# EMG_Sensors_Control.net
KiCad netlist of a schematic drawn in Altium Designer
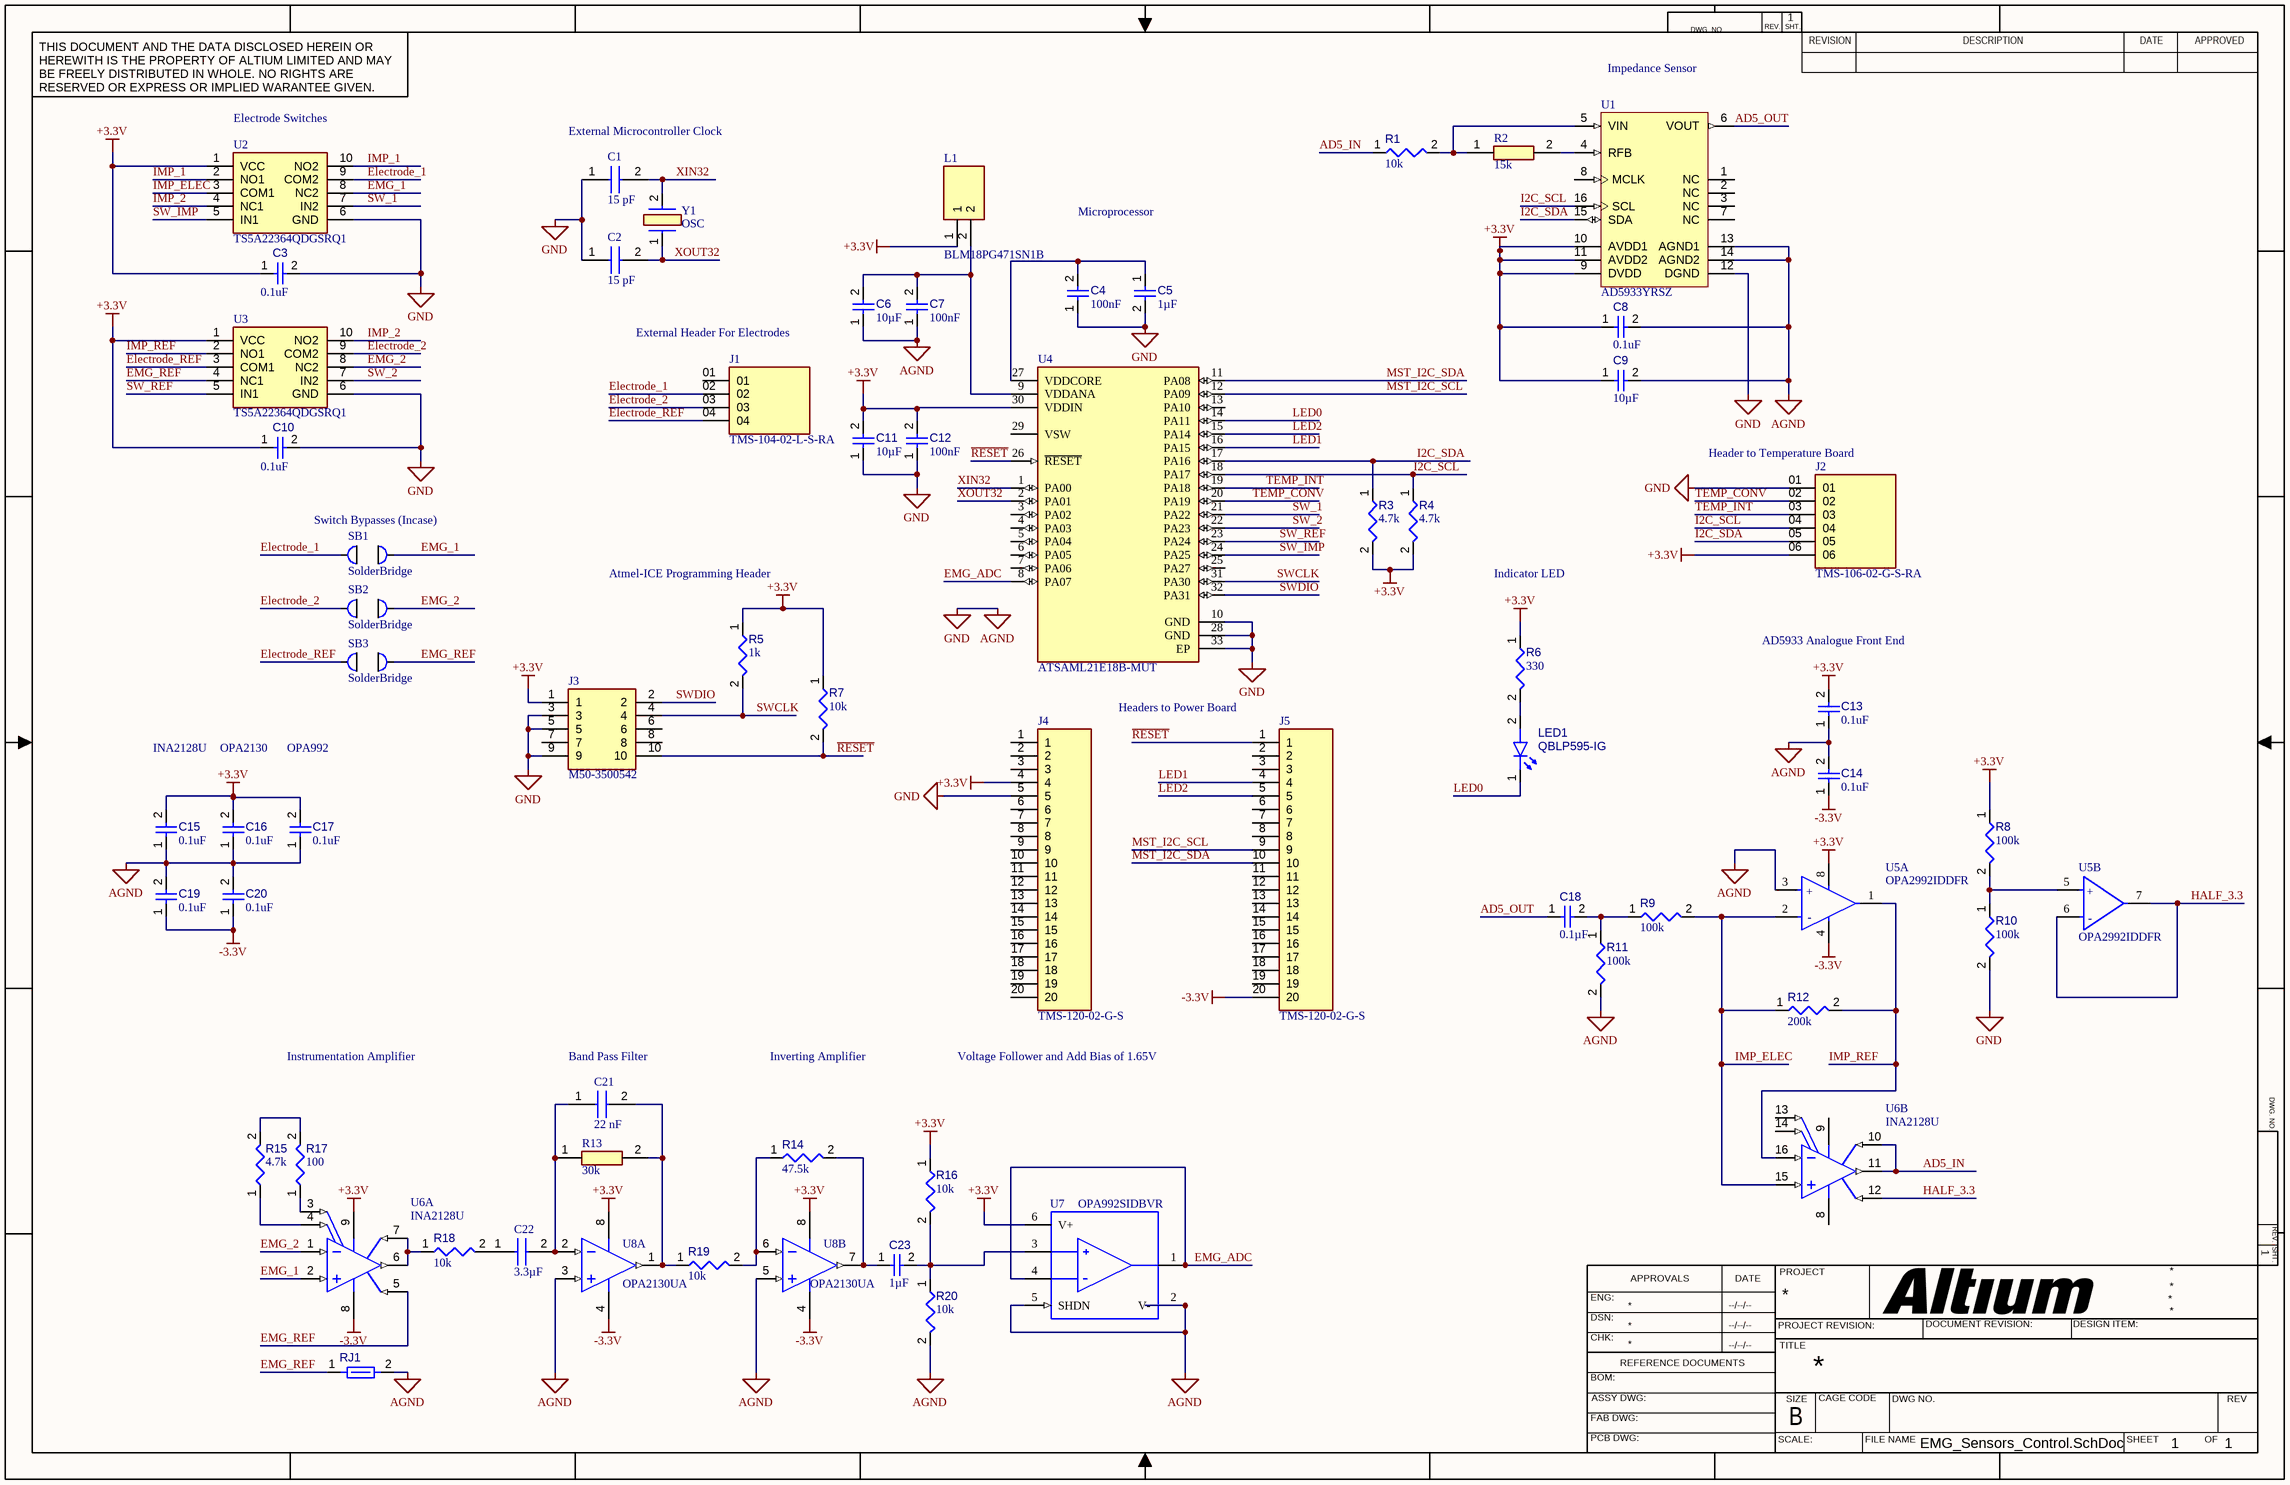
[diagram p0: EMG_Sensors_Control.SchDoc]

(export (version "E")
  (design (tool "Eeschema 10.0.6"))
  (components
    (comp (ref "C1")
      (value "15 pF")
      (footprint "SamacSys:CAPC1005X55N")
      (description "Capacitor 15PF 50V 5% 0402GCM1555C1H150JA16D")
      (fields
        (field (name "MANUFACTURER_PART_NUMBER") "GCM1555C1H150JA16D")
        (field (name "MOUSER PART NUMBER") "81-GCM1555C1H150JA6D")
      )
      (libsource (lib "*") (part "GCM1555C1H150JA16D"))
    )
    (comp (ref "C2")
      (value "15 pF")
      (footprint "SamacSys:CAPC1005X55N")
      (description "Capacitor 15PF 50V 5% 0402GCM1555C1H150JA16D")
      (fields
        (field (name "MANUFACTURER_PART_NUMBER") "GCM1555C1H150JA16D")
        (field (name "MOUSER PART NUMBER") "81-GCM1555C1H150JA6D")
      )
      (libsource (lib "*") (part "GCM1555C1H150JA16D"))
    )
    (comp (ref "C3")
      (value "0.1uF")
      (footprint "CAPC1005X56X25LL10T15")
      (description "Chip Capacitor, 0.1 uF, +/- 5%, 16 V, 0402 (1005 Metric)")
      (fields (field (name "TOLERANCE") "5%") (field (name "Comment") "Capacitor 0.1 uF +/- 5% 16 V 0402"))
      (libsource (lib "Education") (part "CAP-NP-2"))
    )
    (comp (ref "C4")
      (value "100nF")
      (footprint "CAPC1005X56X25LL10T15")
      (description "Chip Capacitor, 0.1 uF, +/- 5%, 16 V, 0402 (1005 Metric)")
      (fields (field (name "TOLERANCE") "5%") (field (name "Comment") "Capacitor 0.1 uF +/- 5% 16 V 0402"))
      (libsource (lib "Education") (part "CAP-NP-2"))
    )
    (comp (ref "C5")
      (value "1µF")
      (footprint "CAPC1608X90X35ML15T15")
      (description "Chip Capacitor, 1 uF, +/- 10%, 16 V, 0603 (1608 Metric)")
      (fields (field (name "TOLERANCE") "10%") (field (name "Comment") "Capacitor 1uF +/- 10% 16V 0603"))
      (libsource (lib "Education") (part "CAP-NP-2"))
    )
    (comp (ref "C6")
      (value "10µF")
      (footprint "CAPC2013X135X45NL10T25")
      (description "Chip Capacitor, 10 uF, +/- 10%, 16 V, 0805 (2012 Metric)")
      (fields (field (name "TOLERANCE") "10%") (field (name "Comment") "Capacitor 10 uF +/- 10% 16 V 0805"))
      (libsource (lib "Education") (part "CAP-NP-2"))
    )
    (comp (ref "C7")
      (value "100nF")
      (footprint "CAPC1005X56X25LL10T15")
      (description "Chip Capacitor, 0.1 uF, +/- 5%, 16 V, 0402 (1005 Metric)")
      (fields (field (name "TOLERANCE") "5%") (field (name "Comment") "Capacitor 0.1 uF +/- 5% 16 V 0402"))
      (libsource (lib "Education") (part "CAP-NP-2"))
    )
    (comp (ref "C8")
      (value "0.1uF")
      (footprint "CAPC1005X56X25LL10T15")
      (description "Chip Capacitor, 0.1 uF, +/- 5%, 16 V, 0402 (1005 Metric)")
      (fields (field (name "TOLERANCE") "5%") (field (name "Comment") "Capacitor 0.1 uF +/- 5% 16 V 0402"))
      (libsource (lib "Education") (part "CAP-NP-2"))
    )
    (comp (ref "C9")
      (value "10µF")
      (footprint "CAPC0603(1608)100_L")
      (description "Chip Capacitor, 10µF +/-20%, 10V, 0603, Thickness 1 mm")
      (fields (field (name "TOLERANCE") "10%") (field (name "Comment") "Capacitor 10µF +/-20% 10V 0603"))
      (libsource (lib "Education") (part "CAP-NP-2"))
    )
    (comp (ref "C10")
      (value "0.1uF")
      (footprint "CAPC1005X56X25LL10T15")
      (description "Chip Capacitor, 0.1 uF, +/- 5%, 16 V, 0402 (1005 Metric)")
      (fields (field (name "TOLERANCE") "5%") (field (name "Comment") "Capacitor 0.1 uF +/- 5% 16 V 0402"))
      (libsource (lib "Education") (part "CAP-NP-2"))
    )
    (comp (ref "C11")
      (value "10µF")
      (footprint "CAPC2013X135X45NL10T25")
      (description "Chip Capacitor, 10 uF, +/- 10%, 16 V, 0805 (2012 Metric)")
      (fields (field (name "TOLERANCE") "10%") (field (name "Comment") "Capacitor 10 uF +/- 10% 16 V 0805"))
      (libsource (lib "Education") (part "CAP-NP-2"))
    )
    (comp (ref "C12")
      (value "100nF")
      (footprint "CAPC1005X56X25LL10T15")
      (description "Chip Capacitor, 0.1 uF, +/- 5%, 16 V, 0402 (1005 Metric)")
      (fields (field (name "TOLERANCE") "5%") (field (name "Comment") "Capacitor 0.1 uF +/- 5% 16 V 0402"))
      (libsource (lib "Education") (part "CAP-NP-2"))
    )
    (comp (ref "C13")
      (value "0.1uF")
      (footprint "CAPC1005X56X25LL10T15")
      (description "Chip Capacitor, 0.1 uF, +/- 5%, 16 V, 0402 (1005 Metric)")
      (fields (field (name "TOLERANCE") "5%") (field (name "Comment") "Capacitor 0.1 uF +/- 5% 16 V 0402"))
      (libsource (lib "Education") (part "CAP-NP-2"))
    )
    (comp (ref "C14")
      (value "0.1uF")
      (footprint "CAPC1005X56X25LL10T15")
      (description "Chip Capacitor, 0.1 uF, +/- 5%, 16 V, 0402 (1005 Metric)")
      (fields (field (name "TOLERANCE") "5%") (field (name "Comment") "Capacitor 0.1 uF +/- 5% 16 V 0402"))
      (libsource (lib "Education") (part "CAP-NP-2"))
    )
    (comp (ref "C15")
      (value "0.1uF")
      (footprint "CAPC1005X56X25LL10T15")
      (description "Chip Capacitor, 0.1 uF, +/- 5%, 16 V, 0402 (1005 Metric)")
      (fields (field (name "TOLERANCE") "5%") (field (name "Comment") "Capacitor 0.1 uF +/- 5% 16 V 0402"))
      (libsource (lib "Education") (part "CAP-NP-2"))
    )
    (comp (ref "C16")
      (value "0.1uF")
      (footprint "CAPC1005X56X25LL10T15")
      (description "Chip Capacitor, 0.1 uF, +/- 5%, 16 V, 0402 (1005 Metric)")
      (fields (field (name "TOLERANCE") "5%") (field (name "Comment") "Capacitor 0.1 uF +/- 5% 16 V 0402"))
      (libsource (lib "Education") (part "CAP-NP-2"))
    )
    (comp (ref "C17")
      (value "0.1uF")
      (footprint "CAPC1005X56X25LL10T15")
      (description "Chip Capacitor, 0.1 uF, +/- 5%, 16 V, 0402 (1005 Metric)")
      (fields (field (name "TOLERANCE") "5%") (field (name "Comment") "Capacitor 0.1 uF +/- 5% 16 V 0402"))
      (libsource (lib "Education") (part "CAP-NP-2"))
    )
    (comp (ref "C18")
      (value "0.1µF")
      (footprint "CAPC1005X55X25LL05T10")
      (description "Chip Capacitor, 1 uF, +/- 10%, 6.3 V, 0402 (1005 Metric)")
      (fields (field (name "TOLERANCE") "10%") (field (name "Comment") "Capacitor 1 uF +/- 10% 6.3 V 0402"))
      (libsource (lib "Education") (part "CAP-NP-2"))
    )
    (comp (ref "C19")
      (value "0.1uF")
      (footprint "CAPC1005X56X25LL10T15")
      (description "Chip Capacitor, 0.1 uF, +/- 5%, 16 V, 0402 (1005 Metric)")
      (fields (field (name "TOLERANCE") "5%") (field (name "Comment") "Capacitor 0.1 uF +/- 5% 16 V 0402"))
      (libsource (lib "Education") (part "CAP-NP-2"))
    )
    (comp (ref "C20")
      (value "0.1uF")
      (footprint "CAPC1005X56X25LL10T15")
      (description "Chip Capacitor, 0.1 uF, +/- 5%, 16 V, 0402 (1005 Metric)")
      (fields (field (name "TOLERANCE") "5%") (field (name "Comment") "Capacitor 0.1 uF +/- 5% 16 V 0402"))
      (libsource (lib "Education") (part "CAP-NP-2"))
    )
    (comp (ref "C21")
      (value "22 nF")
      (footprint "SamacSys:CAPC1005X55N")
      (description "Capacitor 22nF")
      (fields
        (field (name "MANUFACTURER_PART_NUMBER") "GRM155R70J222KA01D")
        (field (name "MOUSER PART NUMBER") "81-GRM155R70J222KA1D")
      )
      (libsource (lib "*") (part "GRM155R70J222KA01D"))
    )
    (comp (ref "C22")
      (value "3.3µF")
      (footprint "SamacSys:C1005_Commercial")
      (description "Capacitor 3.3uF C1005X5R0J335K050BC")
      (fields
        (field (name "MANUFACTURER_PART_NUMBER") "C1005X5R0J335K050BC")
        (field (name "MOUSER PART NUMBER") "810-C1005X5R0J335K")
      )
      (libsource (lib "*") (part "C1005X5R0J335K050BC"))
    )
    (comp (ref "C23")
      (value "1µF")
      (footprint "CAPC1005X55X25LL05T10")
      (description "Chip Capacitor, 1 uF, +/- 10%, 6.3 V, 0402 (1005 Metric)")
      (fields (field (name "TOLERANCE") "10%") (field (name "Comment") "Capacitor 1 uF +/- 10% 6.3 V 0402"))
      (libsource (lib "Education") (part "CAP-NP-2"))
    )
    (comp (ref "J1")
      (value "TMS-104-02-L-S-RA")
      (footprint "SAMTEC_TMS-104-02-L-S-RA")
      (libsource (lib "TMS-104-02-L-S-RA") (part "TMS-104-02-L-S-RA"))
    )
    (comp (ref "J2")
      (value "TMS-106-02-G-S-RA")
      (footprint "SAMTEC_TMS-106-02-G-S-RA")
      (libsource (lib "TMS-106-02-G-S-RA") (part "TMS-106-02-G-S-RA"))
    )
    (comp (ref "J3")
      (value "M50-3500542")
      (footprint "SamacSys:M503500542")
      (description "Connector M50-3500542")
      (fields (field (name "MOUSER PART NUMBER") "855-M50-3500542"))
      (libsource (lib "*") (part "M50-3500542"))
    )
    (comp (ref "J4")
      (value "TMS-120-02-G-S")
      (footprint "SamacSys:TMS-120-YY-XX-S")
      (description "Connector - male needed, place on top board TMS-120-02-G-S")
      (fields (field (name "MOUSER PART NUMBER") "200-TMS12002GS"))
      (libsource (lib "SamacSys") (part "TMS-120-02-G-S"))
    )
    (comp (ref "J5")
      (value "TMS-120-02-G-S")
      (footprint "SamacSys:TMS-120-YY-XX-S")
      (description "Connector - male needed, place on top board TMS-120-02-G-S")
      (fields (field (name "MOUSER PART NUMBER") "200-TMS12002GS"))
      (libsource (lib "SamacSys") (part "TMS-120-02-G-S"))
    )
    (comp (ref "L1")
      (value "BLM18PG471SN1B")
      (footprint "SamacSys:BLM18AG102BH1D")
      (description "Filter BLM18PG471SN1B")
      (fields (field (name "MOUSER PART NUMBER") "81-BLM18PG471SN1B"))
      (libsource (lib "*") (part "BLM18PG471SN1B"))
    )
    (comp (ref "LED1")
      (value "QBLP595-IG")
      (footprint "QTB-QBLP595_V")
      (libsource (lib "Education") (part "LED-KA-2"))
    )
    (comp (ref "R1")
      (value "10k")
      (footprint "RESC1005X40X25ML05T05")
      (description "Chip Resistor, 10 KOhm, +/- 1%, 63 mW, -55 to 155 degC, 0402 (1005 Metric)")
      (fields (field (name "POWER") "63mW") (field (name "TOLERANCE") "1%"))
      (libsource (lib "Education") (part "RES-2"))
    )
    (comp (ref "R2")
      (value "15k")
      (footprint "SamacSys:H2C/H2R")
      (description "Resistor  ERJ-H2RD1502X")
      (fields (field (name "MANUFACTURER_PART_NUMBER") "ERJ-H2RD1502X"))
      (libsource (lib "*") (part "ERJ-H2RD1502X"))
    )
    (comp (ref "R3")
      (value "4.7k")
      (footprint "RESC1005X40X25ML05T05")
      (description "Chip Resistor, 4.7 KOhm, +/- 1%, 0.1 W, -55 to 155 degC, 0402 (1005 Metric)")
      (fields (field (name "POWER") "100mW") (field (name "TOLERANCE") "1%"))
      (libsource (lib "Education") (part "RES-2"))
    )
    (comp (ref "R4")
      (value "4.7k")
      (footprint "RESC1005X40X25ML05T05")
      (description "Chip Resistor, 4.7 KOhm, +/- 1%, 0.1 W, -55 to 155 degC, 0402 (1005 Metric)")
      (fields (field (name "POWER") "100mW") (field (name "TOLERANCE") "1%"))
      (libsource (lib "Education") (part "RES-2"))
    )
    (comp (ref "R5")
      (value "1k")
      (footprint "RESC1005X40X25ML05T05")
      (description "Chip Resistor, 1 KOhm, +/- 1%, 63 mW, -55 to 155 degC, 0402 (1005 Metric)")
      (fields (field (name "POWER") "63mW") (field (name "TOLERANCE") "1%"))
      (libsource (lib "Education") (part "RES-2"))
    )
    (comp (ref "R6")
      (value "330")
      (footprint "RESC0402(1005)_L")
      (description "Chip Resistor, 330 Ohms, +/-5 %, 63 mW, -55 to 155 degC, 0402")
      (fields (field (name "POWER") "63mW") (field (name "TOLERANCE") "5%"))
      (libsource (lib "Education") (part "RES-2"))
    )
    (comp (ref "R7")
      (value "10k")
      (footprint "RESC1005X40X25ML05T05")
      (description "Chip Resistor, 10 KOhm, +/- 1%, 63 mW, -55 to 155 degC, 0402 (1005 Metric)")
      (fields (field (name "POWER") "63mW") (field (name "TOLERANCE") "1%"))
      (libsource (lib "Education") (part "RES-2"))
    )
    (comp (ref "R8")
      (value "100k")
      (footprint "RESC1005X40X25ML05T05")
      (description "Chip Resistor, 100 KOhm, +/- 1%, 0.063 W, -55 to 155 degC, 0402 (1005 Metric)")
      (fields (field (name "TOLERANCE") "1%") (field (name "POWER") "63mW"))
      (libsource (lib "Education") (part "RES-2"))
    )
    (comp (ref "R9")
      (value "100k")
      (footprint "RESC1005X40X25ML05T05")
      (description "Chip Resistor, 100 KOhm, +/- 1%, 0.063 W, -55 to 155 degC, 0402 (1005 Metric)")
      (fields (field (name "TOLERANCE") "1%") (field (name "POWER") "63mW"))
      (libsource (lib "Education") (part "RES-2"))
    )
    (comp (ref "R10")
      (value "100k")
      (footprint "RESC1005X40X25ML05T05")
      (description "Chip Resistor, 100 KOhm, +/- 1%, 0.063 W, -55 to 155 degC, 0402 (1005 Metric)")
      (fields (field (name "TOLERANCE") "1%") (field (name "POWER") "63mW"))
      (libsource (lib "Education") (part "RES-2"))
    )
    (comp (ref "R11")
      (value "100k")
      (footprint "RESC1005X40X25ML05T05")
      (description "Chip Resistor, 1 KOhm, +/- 1%, 63 mW, -55 to 155 degC, 0402 (1005 Metric)")
      (fields (field (name "POWER") "63mW") (field (name "TOLERANCE") "1%"))
      (libsource (lib "Education") (part "RES-2"))
    )
    (comp (ref "R12")
      (value "200k")
      (footprint "RESC0402(1005)_L")
      (description "Chip Resistor, 1 MOhms, +/-1 %, 63 mW, -55 to 155 degC, 0402")
      (fields (field (name "TOLERANCE") "1%") (field (name "POWER") "63mW"))
      (libsource (lib "Education") (part "RES-2"))
    )
    (comp (ref "R13")
      (value "30k")
      (footprint "SamacSys:RESC1005X40N")
      (description "Resistor 30k 0402 SFR01MZPJ303")
      (fields (field (name "MANUFACTURER_PART_NUMBER") "SFR01MZPJ303"))
      (libsource (lib "*") (part "SFR01MZPJ303"))
    )
    (comp (ref "R14")
      (value "47.5k")
      (footprint "RESC0402(1005)_L")
      (description "Chip Resistor, 47,5 kOhms, +/-1 %, 63 mW, -55 to 155 degC, 0402")
      (fields (field (name "POWER") "63mW") (field (name "TOLERANCE") "1%"))
      (libsource (lib "Education") (part "RES-2"))
    )
    (comp (ref "R15")
      (value "4.7k")
      (footprint "RESC1005X40X25ML05T05")
      (description "Chip Resistor, 4.7 KOhm, +/- 1%, 0.1 W, -55 to 155 degC, 0402 (1005 Metric)")
      (fields (field (name "POWER") "100mW") (field (name "TOLERANCE") "1%"))
      (libsource (lib "Education") (part "RES-2"))
    )
    (comp (ref "R16")
      (value "10k")
      (footprint "RESC1005X40X25ML05T05")
      (description "Chip Resistor, 10 KOhm, +/- 1%, 63 mW, -55 to 155 degC, 0402 (1005 Metric)")
      (fields (field (name "POWER") "63mW") (field (name "TOLERANCE") "1%"))
      (libsource (lib "Education") (part "RES-2"))
    )
    (comp (ref "R17")
      (value "100")
      (footprint "RESC0402(1005)_L")
      (description "100R 0.063W 1% 0402 (1005 Metric)  SMD")
      (fields (field (name "TOLERANCE") "1%") (field (name "POWER") "63mW"))
      (libsource (lib "Education") (part "100R2F"))
    )
    (comp (ref "R18")
      (value "10k")
      (footprint "RESC1005X40X25ML05T05")
      (description "Chip Resistor, 10 KOhm, +/- 1%, 63 mW, -55 to 155 degC, 0402 (1005 Metric)")
      (fields (field (name "POWER") "63mW") (field (name "TOLERANCE") "1%"))
      (libsource (lib "Education") (part "RES-2"))
    )
    (comp (ref "R19")
      (value "10k")
      (footprint "RESC1005X40X25ML05T05")
      (description "Chip Resistor, 10 KOhm, +/- 1%, 63 mW, -55 to 155 degC, 0402 (1005 Metric)")
      (fields (field (name "POWER") "63mW") (field (name "TOLERANCE") "1%"))
      (libsource (lib "Education") (part "RES-2"))
    )
    (comp (ref "R20")
      (value "10k")
      (footprint "RESC1005X40X25ML05T05")
      (description "Chip Resistor, 10 KOhm, +/- 1%, 63 mW, -55 to 155 degC, 0402 (1005 Metric)")
      (fields (field (name "POWER") "63mW") (field (name "TOLERANCE") "1%"))
      (libsource (lib "Education") (part "RES-2"))
    )
    (comp (ref "RJ1")
      (value "Net Tie 10x8mil")
      (footprint "New footprint 1")
      (libsource (lib "Education") (part "CMP-00022-00002-2"))
    )
    (comp (ref "SB1")
      (value "SolderBridge")
      (footprint "SolderBridge-Footprint-1")
      (description "Simple open solder bridge")
      (libsource (lib "Education") (part "SolderBridge"))
    )
    (comp (ref "SB2")
      (value "SolderBridge")
      (footprint "SolderBridge-Footprint-1")
      (description "Simple open solder bridge")
      (libsource (lib "Education") (part "SolderBridge"))
    )
    (comp (ref "SB3")
      (value "SolderBridge")
      (footprint "SolderBridge-Footprint-1")
      (description "Simple open solder bridge")
      (libsource (lib "Education") (part "SolderBridge"))
    )
    (comp (ref "U1")
      (value "AD5933YRSZ")
      (footprint "ADI-RS-16_L")
      (description "1 MSPS, 12-Bit Impedance Converter, Network Analyzer, Serial, RS-16, 77 Tube, Pb-Free")
      (libsource (lib "Altium Content Vault") (part "ADI-AD5933-RS-16"))
    )
    (comp (ref "U2")
      (value "TS5A22364QDGSRQ1")
      (footprint "SamacSys:SOP50P490X110-10N")
      (description "Integrated Circuit")
      (fields (field (name "MOUSER PART NUMBER") "595-TS5A22364QDGSRQ1"))
      (libsource (lib "*") (part "TS5A22364QDGSRQ1"))
    )
    (comp (ref "U3")
      (value "TS5A22364QDGSRQ1")
      (footprint "SamacSys:SOP50P490X110-10N")
      (description "Integrated Circuit")
      (fields (field (name "MOUSER PART NUMBER") "595-TS5A22364QDGSRQ1"))
      (libsource (lib "*") (part "TS5A22364QDGSRQ1"))
    )
    (comp (ref "U4")
      (value "ATSAML21E18B-MUT")
      (footprint "FP-PG-IPC_B")
      (description "IC MCU 32BIT 256KB FLASH 32QFN")
      (libsource (lib "Altium Content Vault") (part "b79c866f022c195cb18a64dbd2a129a"))
    )
    (comp (ref "U5")
      (value "OPA2992IDDFR")
      (footprint "FP-DDF0008A-MFG")
      (description "IC OPAMP GP 2 CIRCUIT TSOT23-8")
      (libsource (lib "Altium Content Vault") (part "d5b36c1049528187b1d2197d5d58d7e"))
    )
    (comp (ref "U6")
      (value "INA2128U")
      (footprint "DW0016A_N")
      (fields (field (name "MANUFACTURER") "Texas Instruments"))
      (libsource (lib "Altium Content Vault") (part "TI-INA212XXXX16"))
    )
    (comp (ref "U7")
      (value "OPA992SIDBVR")
      (footprint "FP-DBV0006A-MFG")
      (description "IC OPAMP")
      (libsource (lib "Altium Content Vault") (part "a02ce2c64a2dc138dd09b28dc7c79e9"))
    )
    (comp (ref "U8")
      (value "OPA2130UA")
      (footprint "D0008A_N")
      (fields (field (name "MANUFACTURER") "Texas Instruments"))
      (libsource (lib "Altium Content Vault") (part "TI-OPA-8_2"))
    )
    (comp (ref "Y1")
      (value "OSC")
      (footprint "SamacSys:ABS0716632768KHZT")
      (description "Crystal or Oscillator ABS07-32.768KHZ-T 12.5pF")
      (fields
        (field (name "MANUFACTURER_PART_NUMBER") "ABS07-32.768KHZ-T")
        (field (name "MOUSER PART NUMBER") "815-ABS07-32.768KHZT")
      )
      (libsource (lib "*") (part "ABS07-32.768KHZ-T"))
    )
  )
  (nets
    (net (code "1") (name "+3.3V") (class "Default")
      (node (ref "C10") (pin "1") (pinfunction "1_1") (pintype "passive"))
      (node (ref "C11") (pin "2") (pinfunction "2_2") (pintype "passive"))
      (node (ref "C12") (pin "2") (pinfunction "2_2") (pintype "passive"))
      (node (ref "C13") (pin "2") (pinfunction "2_2") (pintype "passive"))
      (node (ref "C15") (pin "2") (pinfunction "2_2") (pintype "passive"))
      (node (ref "C16") (pin "2") (pinfunction "2_2") (pintype "passive"))
      (node (ref "C17") (pin "2") (pinfunction "2_2") (pintype "passive"))
      (node (ref "C3") (pin "1") (pinfunction "1_1") (pintype "passive"))
      (node (ref "C8") (pin "1") (pinfunction "1_1") (pintype "passive"))
      (node (ref "C9") (pin "1") (pinfunction "1_1") (pintype "passive"))
      (node (ref "J2") (pin "06") (pinfunction "06_06") (pintype "passive"))
      (node (ref "J3") (pin "1") (pinfunction "1_1") (pintype "passive"))
      (node (ref "J4") (pin "4") (pinfunction "4_4") (pintype "passive"))
      (node (ref "L1") (pin "1") (pinfunction "1_1") (pintype "passive"))
      (node (ref "R16") (pin "1") (pinfunction "1_1") (pintype "passive"))
      (node (ref "R3") (pin "2") (pinfunction "2_2") (pintype "passive"))
      (node (ref "R4") (pin "2") (pinfunction "2_2") (pintype "passive"))
      (node (ref "R5") (pin "1") (pinfunction "1_1") (pintype "passive"))
      (node (ref "R6") (pin "1") (pinfunction "1_1") (pintype "passive"))
      (node (ref "R7") (pin "1") (pinfunction "1_1") (pintype "passive"))
      (node (ref "R8") (pin "1") (pinfunction "1_1") (pintype "passive"))
      (node (ref "U1") (pin "10") (pinfunction "AVDD1_10") (pintype "power_in"))
      (node (ref "U1") (pin "11") (pinfunction "AVDD2_11") (pintype "power_in"))
      (node (ref "U1") (pin "9") (pinfunction "DVDD_9") (pintype "power_in"))
      (node (ref "U2") (pin "1") (pinfunction "VCC_1") (pintype "passive"))
      (node (ref "U3") (pin "1") (pinfunction "VCC_1") (pintype "passive"))
      (node (ref "U4") (pin "30") (pinfunction "VDDIN_30") (pintype "power_in"))
      (node (ref "U5") (pin "8") (pinfunction "V+_8") (pintype "power_in"))
      (node (ref "U6") (pin "9") (pinfunction "V+_9") (pintype "power_in"))
      (node (ref "U7") (pin "6") (pinfunction "V+_6") (pintype "power_in"))
      (node (ref "U8") (pin "8") (pinfunction "V+_8") (pintype "power_in"))
    )
    (net (code "2") (name "-3.3V") (class "Default")
      (node (ref "C14") (pin "1") (pinfunction "1_1") (pintype "passive"))
      (node (ref "C19") (pin "1") (pinfunction "1_1") (pintype "passive"))
      (node (ref "C20") (pin "1") (pinfunction "1_1") (pintype "passive"))
      (node (ref "J5") (pin "20") (pinfunction "20_20") (pintype "passive"))
      (node (ref "U5") (pin "4") (pinfunction "V-_4") (pintype "power_in"))
      (node (ref "U6") (pin "8") (pinfunction "V-_8") (pintype "power_in"))
      (node (ref "U8") (pin "4") (pinfunction "V-_4") (pintype "power_in"))
    )
    (net (code "3") (name "/AD5_IN") (class "Default")
      (node (ref "R1") (pin "1") (pinfunction "1_1") (pintype "passive"))
      (node (ref "U6") (pin "10") (pinfunction "SENSEB_10") (pintype "input"))
      (node (ref "U6") (pin "11") (pinfunction "VOB_11") (pintype "output"))
    )
    (net (code "4") (name "/AD5_OUT") (class "Default")
      (node (ref "C18") (pin "1") (pinfunction "1_1") (pintype "passive"))
      (node (ref "U1") (pin "6") (pinfunction "VOUT_6") (pintype "output"))
    )
    (net (code "5") (name "/EMG_1") (class "Default")
      (node (ref "SB1") (pin "1") (pinfunction "1_1") (pintype "passive"))
      (node (ref "U2") (pin "8") (pinfunction "NC2_8") (pintype "passive"))
      (node (ref "U6") (pin "2") (pinfunction "VINA+_2") (pintype "input"))
    )
    (net (code "6") (name "/EMG_2") (class "Default")
      (node (ref "SB2") (pin "1") (pinfunction "1_1") (pintype "passive"))
      (node (ref "U3") (pin "8") (pinfunction "NC2_8") (pintype "passive"))
      (node (ref "U6") (pin "1") (pinfunction "VINA-_1") (pintype "input"))
    )
    (net (code "7") (name "/EMG_ADC") (class "Default")
      (node (ref "U4") (pin "8") (pinfunction "PA07_8") (pintype "bidirectional"))
      (node (ref "U7") (pin "1") (pinfunction "OUT_1") (pintype "passive"))
      (node (ref "U7") (pin "4") (pinfunction "-IN_4") (pintype "tri_state"))
    )
    (net (code "8") (name "/EMG_REF") (class "Default")
      (node (ref "RJ1") (pin "1") (pinfunction "1_1") (pintype "passive"))
      (node (ref "SB3") (pin "1") (pinfunction "1_1") (pintype "passive"))
      (node (ref "U3") (pin "4") (pinfunction "NC1_4") (pintype "passive"))
      (node (ref "U6") (pin "5") (pinfunction "REFA_5") (pintype "input"))
    )
    (net (code "9") (name "/Electrode_1") (class "Default")
      (node (ref "J1") (pin "02") (pinfunction "02_02") (pintype "passive"))
      (node (ref "SB1") (pin "2") (pinfunction "2_2") (pintype "passive"))
      (node (ref "U2") (pin "9") (pinfunction "COM2_9") (pintype "passive"))
    )
    (net (code "10") (name "/Electrode_2") (class "Default")
      (node (ref "J1") (pin "03") (pinfunction "03_03") (pintype "passive"))
      (node (ref "SB2") (pin "2") (pinfunction "2_2") (pintype "passive"))
      (node (ref "U3") (pin "9") (pinfunction "COM2_9") (pintype "passive"))
    )
    (net (code "11") (name "/Electrode_REF") (class "Default")
      (node (ref "J1") (pin "04") (pinfunction "04_04") (pintype "passive"))
      (node (ref "SB3") (pin "2") (pinfunction "2_2") (pintype "passive"))
      (node (ref "U3") (pin "3") (pinfunction "COM1_3") (pintype "passive"))
    )
    (net (code "12") (name "/HALF_3.3") (class "Default")
      (node (ref "U5") (pin "6") (pinfunction "IN2-_6") (pintype "tri_state"))
      (node (ref "U5") (pin "7") (pinfunction "OUT2_7") (pintype "passive"))
      (node (ref "U6") (pin "12") (pinfunction "REFB_12") (pintype "input"))
    )
    (net (code "13") (name "/I2C_SCL") (class "Default")
      (node (ref "J2") (pin "04") (pinfunction "04_04") (pintype "passive"))
      (node (ref "R4") (pin "1") (pinfunction "1_1") (pintype "passive"))
      (node (ref "U1") (pin "16") (pinfunction "SCL_16") (pintype "input"))
      (node (ref "U4") (pin "18") (pinfunction "PA17_18") (pintype "bidirectional"))
    )
    (net (code "14") (name "/I2C_SDA") (class "Default")
      (node (ref "J2") (pin "05") (pinfunction "05_05") (pintype "passive"))
      (node (ref "R3") (pin "1") (pinfunction "1_1") (pintype "passive"))
      (node (ref "U1") (pin "15") (pinfunction "SDA_15") (pintype "bidirectional"))
      (node (ref "U4") (pin "17") (pinfunction "PA16_17") (pintype "bidirectional"))
    )
    (net (code "15") (name "/IMP_1") (class "Default")
      (node (ref "U2") (pin "10") (pinfunction "NO2_10") (pintype "passive"))
      (node (ref "U2") (pin "2") (pinfunction "NO1_2") (pintype "passive"))
    )
    (net (code "16") (name "/IMP_2") (class "Default")
      (node (ref "U2") (pin "4") (pinfunction "NC1_4") (pintype "passive"))
      (node (ref "U3") (pin "10") (pinfunction "NO2_10") (pintype "passive"))
    )
    (net (code "17") (name "/IMP_ELEC") (class "Default")
      (node (ref "R12") (pin "1") (pinfunction "1_1") (pintype "passive"))
      (node (ref "R9") (pin "2") (pinfunction "2_2") (pintype "passive"))
      (node (ref "U2") (pin "3") (pinfunction "COM1_3") (pintype "passive"))
      (node (ref "U5") (pin "2") (pinfunction "IN1-_2") (pintype "tri_state"))
      (node (ref "U6") (pin "15") (pinfunction "VINB+_15") (pintype "input"))
    )
    (net (code "18") (name "/IMP_REF") (class "Default")
      (node (ref "R12") (pin "2") (pinfunction "2_2") (pintype "passive"))
      (node (ref "U3") (pin "2") (pinfunction "NO1_2") (pintype "passive"))
      (node (ref "U5") (pin "1") (pinfunction "OUT1_1") (pintype "passive"))
      (node (ref "U6") (pin "16") (pinfunction "VINB-_16") (pintype "input"))
    )
    (net (code "19") (name "/LED0") (class "Default")
      (node (ref "LED1") (pin "1") (pinfunction "K_1") (pintype "passive"))
      (node (ref "U4") (pin "14") (pinfunction "PA11_14") (pintype "bidirectional"))
    )
    (net (code "20") (name "/LED1") (class "Default")
      (node (ref "J5") (pin "4") (pinfunction "4_4") (pintype "passive"))
      (node (ref "U4") (pin "16") (pinfunction "PA15_16") (pintype "bidirectional"))
    )
    (net (code "21") (name "/LED2") (class "Default")
      (node (ref "J5") (pin "5") (pinfunction "5_5") (pintype "passive"))
      (node (ref "U4") (pin "15") (pinfunction "PA14_15") (pintype "bidirectional"))
    )
    (net (code "22") (name "/MST_I2C_SCL") (class "Default")
      (node (ref "J5") (pin "9") (pinfunction "9_9") (pintype "passive"))
      (node (ref "U4") (pin "12") (pinfunction "PA09_12") (pintype "bidirectional"))
    )
    (net (code "23") (name "/MST_I2C_SDA") (class "Default")
      (node (ref "J5") (pin "10") (pinfunction "10_10") (pintype "passive"))
      (node (ref "U4") (pin "11") (pinfunction "PA08_11") (pintype "bidirectional"))
    )
    (net (code "24") (name "/SWCLK") (class "Default")
      (node (ref "J3") (pin "4") (pinfunction "4_4") (pintype "passive"))
      (node (ref "R5") (pin "2") (pinfunction "2_2") (pintype "passive"))
      (node (ref "U4") (pin "31") (pinfunction "PA30_31") (pintype "bidirectional"))
    )
    (net (code "25") (name "/SWDIO") (class "Default")
      (node (ref "J3") (pin "2") (pinfunction "2_2") (pintype "passive"))
      (node (ref "U4") (pin "32") (pinfunction "PA31_32") (pintype "bidirectional"))
    )
    (net (code "26") (name "/SW_1") (class "Default")
      (node (ref "U2") (pin "7") (pinfunction "IN2_7") (pintype "passive"))
      (node (ref "U4") (pin "21") (pinfunction "PA22_21") (pintype "bidirectional"))
    )
    (net (code "27") (name "/SW_2") (class "Default")
      (node (ref "U3") (pin "7") (pinfunction "IN2_7") (pintype "passive"))
      (node (ref "U4") (pin "22") (pinfunction "PA23_22") (pintype "bidirectional"))
    )
    (net (code "28") (name "/SW_IMP") (class "Default")
      (node (ref "U2") (pin "5") (pinfunction "IN1_5") (pintype "passive"))
      (node (ref "U4") (pin "24") (pinfunction "PA25_24") (pintype "bidirectional"))
    )
    (net (code "29") (name "/SW_REF") (class "Default")
      (node (ref "U3") (pin "5") (pinfunction "IN1_5") (pintype "passive"))
      (node (ref "U4") (pin "23") (pinfunction "PA24_23") (pintype "bidirectional"))
    )
    (net (code "30") (name "/TEMP_CONV") (class "Default")
      (node (ref "J2") (pin "02") (pinfunction "02_02") (pintype "passive"))
      (node (ref "U4") (pin "20") (pinfunction "PA19_20") (pintype "bidirectional"))
    )
    (net (code "31") (name "/TEMP_INT") (class "Default")
      (node (ref "J2") (pin "03") (pinfunction "03_03") (pintype "passive"))
      (node (ref "U4") (pin "19") (pinfunction "PA18_19") (pintype "bidirectional"))
    )
    (net (code "32") (name "/XIN32") (class "Default")
      (node (ref "C1") (pin "2") (pinfunction "2_2") (pintype "passive"))
      (node (ref "U4") (pin "1") (pinfunction "PA00_1") (pintype "bidirectional"))
      (node (ref "Y1") (pin "2") (pinfunction "2_2") (pintype "passive"))
    )
    (net (code "33") (name "/XOUT32") (class "Default")
      (node (ref "C2") (pin "2") (pinfunction "2_2") (pintype "passive"))
      (node (ref "U4") (pin "2") (pinfunction "PA01_2") (pintype "bidirectional"))
      (node (ref "Y1") (pin "1") (pinfunction "1_1") (pintype "passive"))
    )
    (net (code "34") (name "/~{RESET}") (class "Default")
      (node (ref "J3") (pin "10") (pinfunction "10_10") (pintype "passive"))
      (node (ref "J5") (pin "1") (pinfunction "1_1") (pintype "passive"))
      (node (ref "R7") (pin "2") (pinfunction "2_2") (pintype "passive"))
      (node (ref "U4") (pin "26") (pinfunction "~{RESET}_26") (pintype "input"))
    )
    (net (code "35") (name "AGND") (class "Default")
      (node (ref "C1") (pin "1") (pinfunction "1_1") (pintype "passive"))
      (node (ref "C10") (pin "2") (pinfunction "2_2") (pintype "passive"))
      (node (ref "C11") (pin "1") (pinfunction "1_1") (pintype "passive"))
      (node (ref "C12") (pin "1") (pinfunction "1_1") (pintype "passive"))
      (node (ref "C13") (pin "1") (pinfunction "1_1") (pintype "passive"))
      (node (ref "C14") (pin "2") (pinfunction "2_2") (pintype "passive"))
      (node (ref "C15") (pin "1") (pinfunction "1_1") (pintype "passive"))
      (node (ref "C16") (pin "1") (pinfunction "1_1") (pintype "passive"))
      (node (ref "C17") (pin "1") (pinfunction "1_1") (pintype "passive"))
      (node (ref "C19") (pin "2") (pinfunction "2_2") (pintype "passive"))
      (node (ref "C2") (pin "1") (pinfunction "1_1") (pintype "passive"))
      (node (ref "C20") (pin "2") (pinfunction "2_2") (pintype "passive"))
      (node (ref "C3") (pin "2") (pinfunction "2_2") (pintype "passive"))
      (node (ref "C4") (pin "1") (pinfunction "1_1") (pintype "passive"))
      (node (ref "C5") (pin "2") (pinfunction "2_2") (pintype "passive"))
      (node (ref "C6") (pin "1") (pinfunction "1_1") (pintype "passive"))
      (node (ref "C7") (pin "1") (pinfunction "1_1") (pintype "passive"))
      (node (ref "C8") (pin "2") (pinfunction "2_2") (pintype "passive"))
      (node (ref "C9") (pin "2") (pinfunction "2_2") (pintype "passive"))
      (node (ref "J2") (pin "01") (pinfunction "01_01") (pintype "passive"))
      (node (ref "J3") (pin "3") (pinfunction "3_3") (pintype "passive"))
      (node (ref "J3") (pin "5") (pinfunction "5_5") (pintype "passive"))
      (node (ref "J3") (pin "9") (pinfunction "9_9") (pintype "passive"))
      (node (ref "J4") (pin "5") (pinfunction "5_5") (pintype "passive"))
      (node (ref "R10") (pin "2") (pinfunction "2_2") (pintype "passive"))
      (node (ref "R11") (pin "2") (pinfunction "2_2") (pintype "passive"))
      (node (ref "R20") (pin "2") (pinfunction "2_2") (pintype "passive"))
      (node (ref "RJ1") (pin "2") (pinfunction "2_2") (pintype "passive"))
      (node (ref "U1") (pin "12") (pinfunction "DGND_12") (pintype "power_in"))
      (node (ref "U1") (pin "13") (pinfunction "AGND1_13") (pintype "power_in"))
      (node (ref "U1") (pin "14") (pinfunction "AGND2_14") (pintype "power_in"))
      (node (ref "U2") (pin "6") (pinfunction "GND_6") (pintype "passive"))
      (node (ref "U3") (pin "6") (pinfunction "GND_6") (pintype "passive"))
      (node (ref "U4") (pin "10") (pinfunction "GND_10") (pintype "power_in"))
      (node (ref "U4") (pin "28") (pinfunction "GND_28") (pintype "power_in"))
      (node (ref "U4") (pin "33") (pinfunction "EP_33") (pintype "passive"))
      (node (ref "U5") (pin "3") (pinfunction "IN1+_3") (pintype "tri_state"))
      (node (ref "U7") (pin "2") (pinfunction "V-_2") (pintype "power_in"))
      (node (ref "U7") (pin "5") (pinfunction "SHDN_5") (pintype "input"))
      (node (ref "U8") (pin "3") (pinfunction "IN_A+_3") (pintype "input"))
      (node (ref "U8") (pin "5") (pinfunction "IN_B+_5") (pintype "input"))
    )
    (net (code "36") (name "Net-(C18-Pad2)") (class "Default")
      (node (ref "C18") (pin "2") (pinfunction "2_2") (pintype "passive"))
      (node (ref "R11") (pin "1") (pinfunction "1_1") (pintype "passive"))
      (node (ref "R9") (pin "1") (pinfunction "1_1") (pintype "passive"))
    )
    (net (code "37") (name "Net-(C22-Pad1)") (class "Default")
      (node (ref "C22") (pin "1") (pinfunction "1_1") (pintype "passive"))
      (node (ref "R18") (pin "2") (pinfunction "2_2") (pintype "passive"))
    )
    (net (code "38") (name "Net-(LED1-A)") (class "Default")
      (node (ref "LED1") (pin "2") (pinfunction "A_2") (pintype "passive"))
      (node (ref "R6") (pin "2") (pinfunction "2_2") (pintype "passive"))
    )
    (net (code "39") (name "Net-(R15-Pad1)") (class "Default")
      (node (ref "R15") (pin "1") (pinfunction "1_1") (pintype "passive"))
      (node (ref "U6") (pin "4") (pinfunction "RGA_4") (pintype "input"))
    )
    (net (code "40") (name "Net-(R15-Pad2)") (class "Default")
      (node (ref "R15") (pin "2") (pinfunction "2_2") (pintype "passive"))
      (node (ref "R17") (pin "2") (pinfunction "2_2") (pintype "passive"))
    )
    (net (code "41") (name "Net-(R17-Pad1)") (class "Default")
      (node (ref "R17") (pin "1") (pinfunction "1_1") (pintype "passive"))
      (node (ref "U6") (pin "3") (pinfunction "RGA_3") (pintype "input"))
    )
    (net (code "42") (name "Net-(U1-RFB)") (class "Default")
      (node (ref "R2") (pin "2") (pinfunction "2_2") (pintype "passive"))
      (node (ref "U1") (pin "4") (pinfunction "RFB_4") (pintype "input"))
    )
    (net (code "43") (name "Net-(U1-VIN)") (class "Default")
      (node (ref "R1") (pin "2") (pinfunction "2_2") (pintype "passive"))
      (node (ref "R2") (pin "1") (pinfunction "1_1") (pintype "passive"))
      (node (ref "U1") (pin "5") (pinfunction "VIN_5") (pintype "input"))
    )
    (net (code "44") (name "Net-(U4-VDDANA)") (class "Default")
      (node (ref "C6") (pin "2") (pinfunction "2_2") (pintype "passive"))
      (node (ref "C7") (pin "2") (pinfunction "2_2") (pintype "passive"))
      (node (ref "L1") (pin "2") (pinfunction "2_2") (pintype "passive"))
      (node (ref "U4") (pin "9") (pinfunction "VDDANA_9") (pintype "power_in"))
    )
    (net (code "45") (name "Net-(U4-VDDCORE)") (class "Default")
      (node (ref "C4") (pin "2") (pinfunction "2_2") (pintype "passive"))
      (node (ref "C5") (pin "1") (pinfunction "1_1") (pintype "passive"))
      (node (ref "U4") (pin "27") (pinfunction "VDDCORE_27") (pintype "power_in"))
    )
    (net (code "46") (name "Net-(U5B-IN2+)") (class "Default")
      (node (ref "R10") (pin "1") (pinfunction "1_1") (pintype "passive"))
      (node (ref "R8") (pin "2") (pinfunction "2_2") (pintype "passive"))
      (node (ref "U5") (pin "5") (pinfunction "IN2+_5") (pintype "tri_state"))
    )
    (net (code "47") (name "Net-(U6A-SENSEA)") (class "Default")
      (node (ref "R18") (pin "1") (pinfunction "1_1") (pintype "passive"))
      (node (ref "U6") (pin "6") (pinfunction "VOA_6") (pintype "output"))
      (node (ref "U6") (pin "7") (pinfunction "SENSEA_7") (pintype "input"))
    )
    (net (code "48") (name "Net-(U7-+IN)") (class "Default")
      (node (ref "C23") (pin "2") (pinfunction "2_2") (pintype "passive"))
      (node (ref "R16") (pin "2") (pinfunction "2_2") (pintype "passive"))
      (node (ref "R20") (pin "1") (pinfunction "1_1") (pintype "passive"))
      (node (ref "U7") (pin "3") (pinfunction "+IN_3") (pintype "tri_state"))
    )
    (net (code "49") (name "Net-(U8A-IN_A-)") (class "Default")
      (node (ref "C21") (pin "1") (pinfunction "1_1") (pintype "passive"))
      (node (ref "C22") (pin "2") (pinfunction "2_2") (pintype "passive"))
      (node (ref "R13") (pin "1") (pinfunction "1_1") (pintype "passive"))
      (node (ref "U8") (pin "2") (pinfunction "IN_A-_2") (pintype "input"))
    )
    (net (code "50") (name "Net-(U8A-OUT_A)") (class "Default")
      (node (ref "C21") (pin "2") (pinfunction "2_2") (pintype "passive"))
      (node (ref "R13") (pin "2") (pinfunction "2_2") (pintype "passive"))
      (node (ref "R19") (pin "1") (pinfunction "1_1") (pintype "passive"))
      (node (ref "U8") (pin "1") (pinfunction "OUT_A_1") (pintype "output"))
    )
    (net (code "51") (name "Net-(U8B-IN_B-)") (class "Default")
      (node (ref "R14") (pin "1") (pinfunction "1_1") (pintype "passive"))
      (node (ref "R19") (pin "2") (pinfunction "2_2") (pintype "passive"))
      (node (ref "U8") (pin "6") (pinfunction "IN_B-_6") (pintype "input"))
    )
    (net (code "52") (name "Net-(U8B-OUT_B)") (class "Default")
      (node (ref "C23") (pin "1") (pinfunction "1_1") (pintype "passive"))
      (node (ref "R14") (pin "2") (pinfunction "2_2") (pintype "passive"))
      (node (ref "U8") (pin "7") (pinfunction "OUT_B_7") (pintype "output"))
    )
    (net (code "53") (name "unconnected-(J1-Pad01)") (class "Default")
      (node (ref "J1") (pin "01") (pinfunction "01_01") (pintype "passive"))
    )
    (net (code "54") (name "unconnected-(J3-Pad6)") (class "Default")
      (node (ref "J3") (pin "6") (pinfunction "6_6") (pintype "passive"))
    )
    (net (code "55") (name "unconnected-(J3-Pad7)") (class "Default")
      (node (ref "J3") (pin "7") (pinfunction "7_7") (pintype "passive"))
    )
    (net (code "56") (name "unconnected-(J3-Pad8)") (class "Default")
      (node (ref "J3") (pin "8") (pinfunction "8_8") (pintype "passive"))
    )
    (net (code "57") (name "unconnected-(J4-Pad1)") (class "Default")
      (node (ref "J4") (pin "1") (pinfunction "1_1") (pintype "passive"))
    )
    (net (code "58") (name "unconnected-(J4-Pad2)") (class "Default")
      (node (ref "J4") (pin "2") (pinfunction "2_2") (pintype "passive"))
    )
    (net (code "59") (name "unconnected-(J4-Pad3)") (class "Default")
      (node (ref "J4") (pin "3") (pinfunction "3_3") (pintype "passive"))
    )
    (net (code "60") (name "unconnected-(J4-Pad6)") (class "Default")
      (node (ref "J4") (pin "6") (pinfunction "6_6") (pintype "passive"))
    )
    (net (code "61") (name "unconnected-(J4-Pad7)") (class "Default")
      (node (ref "J4") (pin "7") (pinfunction "7_7") (pintype "passive"))
    )
    (net (code "62") (name "unconnected-(J4-Pad8)") (class "Default")
      (node (ref "J4") (pin "8") (pinfunction "8_8") (pintype "passive"))
    )
    (net (code "63") (name "unconnected-(J4-Pad9)") (class "Default")
      (node (ref "J4") (pin "9") (pinfunction "9_9") (pintype "passive"))
    )
    (net (code "64") (name "unconnected-(J4-Pad10)") (class "Default")
      (node (ref "J4") (pin "10") (pinfunction "10_10") (pintype "passive"))
    )
    (net (code "65") (name "unconnected-(J4-Pad11)") (class "Default")
      (node (ref "J4") (pin "11") (pinfunction "11_11") (pintype "passive"))
    )
    (net (code "66") (name "unconnected-(J4-Pad12)") (class "Default")
      (node (ref "J4") (pin "12") (pinfunction "12_12") (pintype "passive"))
    )
    (net (code "67") (name "unconnected-(J4-Pad13)") (class "Default")
      (node (ref "J4") (pin "13") (pinfunction "13_13") (pintype "passive"))
    )
    (net (code "68") (name "unconnected-(J4-Pad14)") (class "Default")
      (node (ref "J4") (pin "14") (pinfunction "14_14") (pintype "passive"))
    )
    (net (code "69") (name "unconnected-(J4-Pad15)") (class "Default")
      (node (ref "J4") (pin "15") (pinfunction "15_15") (pintype "passive"))
    )
    (net (code "70") (name "unconnected-(J4-Pad16)") (class "Default")
      (node (ref "J4") (pin "16") (pinfunction "16_16") (pintype "passive"))
    )
    (net (code "71") (name "unconnected-(J4-Pad17)") (class "Default")
      (node (ref "J4") (pin "17") (pinfunction "17_17") (pintype "passive"))
    )
    (net (code "72") (name "unconnected-(J4-Pad18)") (class "Default")
      (node (ref "J4") (pin "18") (pinfunction "18_18") (pintype "passive"))
    )
    (net (code "73") (name "unconnected-(J4-Pad19)") (class "Default")
      (node (ref "J4") (pin "19") (pinfunction "19_19") (pintype "passive"))
    )
    (net (code "74") (name "unconnected-(J4-Pad20)") (class "Default")
      (node (ref "J4") (pin "20") (pinfunction "20_20") (pintype "passive"))
    )
    (net (code "75") (name "unconnected-(J5-Pad2)") (class "Default")
      (node (ref "J5") (pin "2") (pinfunction "2_2") (pintype "passive"))
    )
    (net (code "76") (name "unconnected-(J5-Pad3)") (class "Default")
      (node (ref "J5") (pin "3") (pinfunction "3_3") (pintype "passive"))
    )
    (net (code "77") (name "unconnected-(J5-Pad6)") (class "Default")
      (node (ref "J5") (pin "6") (pinfunction "6_6") (pintype "passive"))
    )
    (net (code "78") (name "unconnected-(J5-Pad7)") (class "Default")
      (node (ref "J5") (pin "7") (pinfunction "7_7") (pintype "passive"))
    )
    (net (code "79") (name "unconnected-(J5-Pad8)") (class "Default")
      (node (ref "J5") (pin "8") (pinfunction "8_8") (pintype "passive"))
    )
    (net (code "80") (name "unconnected-(J5-Pad11)") (class "Default")
      (node (ref "J5") (pin "11") (pinfunction "11_11") (pintype "passive"))
    )
    (net (code "81") (name "unconnected-(J5-Pad12)") (class "Default")
      (node (ref "J5") (pin "12") (pinfunction "12_12") (pintype "passive"))
    )
    (net (code "82") (name "unconnected-(J5-Pad13)") (class "Default")
      (node (ref "J5") (pin "13") (pinfunction "13_13") (pintype "passive"))
    )
    (net (code "83") (name "unconnected-(J5-Pad14)") (class "Default")
      (node (ref "J5") (pin "14") (pinfunction "14_14") (pintype "passive"))
    )
    (net (code "84") (name "unconnected-(J5-Pad15)") (class "Default")
      (node (ref "J5") (pin "15") (pinfunction "15_15") (pintype "passive"))
    )
    (net (code "85") (name "unconnected-(J5-Pad16)") (class "Default")
      (node (ref "J5") (pin "16") (pinfunction "16_16") (pintype "passive"))
    )
    (net (code "86") (name "unconnected-(J5-Pad17)") (class "Default")
      (node (ref "J5") (pin "17") (pinfunction "17_17") (pintype "passive"))
    )
    (net (code "87") (name "unconnected-(J5-Pad18)") (class "Default")
      (node (ref "J5") (pin "18") (pinfunction "18_18") (pintype "passive"))
    )
    (net (code "88") (name "unconnected-(J5-Pad19)") (class "Default")
      (node (ref "J5") (pin "19") (pinfunction "19_19") (pintype "passive"))
    )
    (net (code "89") (name "unconnected-(U1-MCLK-Pad8)") (class "Default")
      (node (ref "U1") (pin "8") (pinfunction "MCLK_8") (pintype "input"))
    )
    (net (code "90") (name "unconnected-(U1-NC-Pad1)") (class "Default")
      (node (ref "U1") (pin "1") (pinfunction "NC_1") (pintype "passive"))
    )
    (net (code "91") (name "unconnected-(U1-NC-Pad2)") (class "Default")
      (node (ref "U1") (pin "2") (pinfunction "NC_2") (pintype "passive"))
    )
    (net (code "92") (name "unconnected-(U1-NC-Pad3)") (class "Default")
      (node (ref "U1") (pin "3") (pinfunction "NC_3") (pintype "passive"))
    )
    (net (code "93") (name "unconnected-(U1-NC-Pad7)") (class "Default")
      (node (ref "U1") (pin "7") (pinfunction "NC_7") (pintype "passive"))
    )
    (net (code "94") (name "unconnected-(U4-PA02-Pad3)") (class "Default")
      (node (ref "U4") (pin "3") (pinfunction "PA02_3") (pintype "bidirectional"))
    )
    (net (code "95") (name "unconnected-(U4-PA03-Pad4)") (class "Default")
      (node (ref "U4") (pin "4") (pinfunction "PA03_4") (pintype "bidirectional"))
    )
    (net (code "96") (name "unconnected-(U4-PA04-Pad5)") (class "Default")
      (node (ref "U4") (pin "5") (pinfunction "PA04_5") (pintype "bidirectional"))
    )
    (net (code "97") (name "unconnected-(U4-PA05-Pad6)") (class "Default")
      (node (ref "U4") (pin "6") (pinfunction "PA05_6") (pintype "bidirectional"))
    )
    (net (code "98") (name "unconnected-(U4-PA06-Pad7)") (class "Default")
      (node (ref "U4") (pin "7") (pinfunction "PA06_7") (pintype "bidirectional"))
    )
    (net (code "99") (name "unconnected-(U4-PA10-Pad13)") (class "Default")
      (node (ref "U4") (pin "13") (pinfunction "PA10_13") (pintype "bidirectional"))
    )
    (net (code "100") (name "unconnected-(U4-PA27-Pad25)") (class "Default")
      (node (ref "U4") (pin "25") (pinfunction "PA27_25") (pintype "bidirectional"))
    )
    (net (code "101") (name "unconnected-(U4-VSW-Pad29)") (class "Default")
      (node (ref "U4") (pin "29") (pinfunction "VSW_29") (pintype "power_in"))
    )
    (net (code "102") (name "unconnected-(U6B-RGB-Pad13)") (class "Default")
      (node (ref "U6") (pin "13") (pinfunction "RGB_13") (pintype "input"))
    )
    (net (code "103") (name "unconnected-(U6B-RGB-Pad14)") (class "Default")
      (node (ref "U6") (pin "14") (pinfunction "RGB_14") (pintype "input"))
    )
    (net (code "104") (name "unconnected-(U6B-V+-Pad9)") (class "Default")
      (node (ref "U6") (pin "9") (pinfunction "V+_9") (pintype "power_in"))
    )
    (net (code "105") (name "unconnected-(U6B-V--Pad8)") (class "Default")
      (node (ref "U6") (pin "8") (pinfunction "V-_8") (pintype "power_in"))
    )
  )
)
